# Schematics.net
KiCad netlist of a schematic drawn in Altium Designer
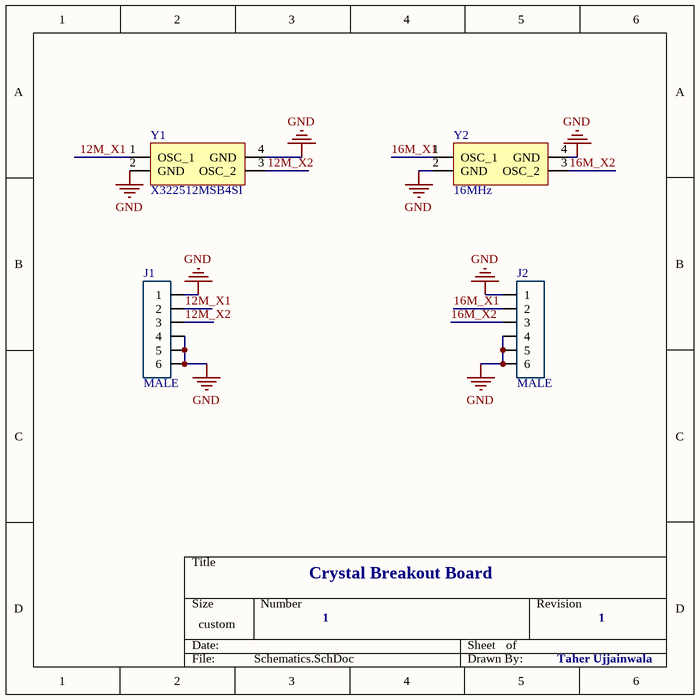
[diagram p0: Schematics.SchDoc]

(export (version "E")
  (design (tool "Eeschema 10.0.6"))
  (components
    (comp (ref "J1")
      (value "MALE")
      (footprint "6_PIN_100MIL")
      (description "Male header- 6 pin 1 row- through Hole")
      (fields (field (name "LCSC PART#") "C37208"))
      (libsource (lib "") (part "JF_6_PIN_MALE_1"))
    )
    (comp (ref "J2")
      (value "MALE")
      (footprint "6_PIN_100MIL")
      (description "Male header- 6 pin 1 row- through Hole")
      (fields (field (name "LCSC PART#") "C37208"))
      (libsource (lib "ECEN5730Lib_JLC_2022_07") (part "JF_6_PIN_MALE"))
    )
    (comp (ref "Y1")
      (value "X322512MSB4SI")
      (footprint "Crystal resonator")
      (description "SMD Crystal Resonators 12MHz ±10ppm SMD-3225_4P RoHS")
      (fields (field (name "LCSC PART#") "C9002"))
      (libsource (lib "ECEN5730Lib_JLC_2022_07") (part "X_12MHz_Res"))
    )
    (comp (ref "Y2")
      (value "16MHz")
      (footprint "Crystal resonator")
      (description "±10ppm 16000000Hz -40℃~85℃ 贴片无源晶振 60Ω 9pF SMD3225-4P Crystals ROHS")
      (fields (field (name "LCSC PART#") "C13738") (field (name "MFR PART #") "X322516MLB4SI"))
      (libsource (lib "ECEN5730Lib_JLC_2022_07") (part "X_16Mhz_Res"))
    )
  )
  (nets
    (net (code "1") (name "/12M_X1") (class "Default")
      (node (ref "J1") (pin "2") (pinfunction "2_2") (pintype "passive"))
      (node (ref "Y1") (pin "1") (pinfunction "OSC_1_1") (pintype "passive"))
    )
    (net (code "2") (name "/12M_X2") (class "Default")
      (node (ref "J1") (pin "3") (pinfunction "3_3") (pintype "passive"))
      (node (ref "Y1") (pin "3") (pinfunction "OSC_2_3") (pintype "passive"))
    )
    (net (code "3") (name "/16M_X1") (class "Default")
      (node (ref "J2") (pin "2") (pinfunction "2_2") (pintype "passive"))
      (node (ref "Y2") (pin "1") (pinfunction "OSC_1_1") (pintype "passive"))
    )
    (net (code "4") (name "/16M_X2") (class "Default")
      (node (ref "J2") (pin "3") (pinfunction "3_3") (pintype "passive"))
      (node (ref "Y2") (pin "3") (pinfunction "OSC_2_3") (pintype "passive"))
    )
    (net (code "5") (name "GND") (class "Default")
      (node (ref "J1") (pin "1") (pinfunction "1_1") (pintype "passive"))
      (node (ref "J1") (pin "4") (pinfunction "4_4") (pintype "passive"))
      (node (ref "J1") (pin "5") (pinfunction "5_5") (pintype "passive"))
      (node (ref "J1") (pin "6") (pinfunction "6_6") (pintype "passive"))
      (node (ref "J2") (pin "1") (pinfunction "1_1") (pintype "passive"))
      (node (ref "J2") (pin "4") (pinfunction "4_4") (pintype "passive"))
      (node (ref "J2") (pin "5") (pinfunction "5_5") (pintype "passive"))
      (node (ref "J2") (pin "6") (pinfunction "6_6") (pintype "passive"))
      (node (ref "Y1") (pin "2") (pinfunction "GND_2") (pintype "passive"))
      (node (ref "Y1") (pin "4") (pinfunction "GND_4") (pintype "passive"))
      (node (ref "Y2") (pin "2") (pinfunction "GND_2") (pintype "passive"))
      (node (ref "Y2") (pin "4") (pinfunction "GND_4") (pintype "passive"))
    )
  )
)
